# ATMega16U2-MU_1.net
KiCad netlist of a schematic drawn in Altium Designer
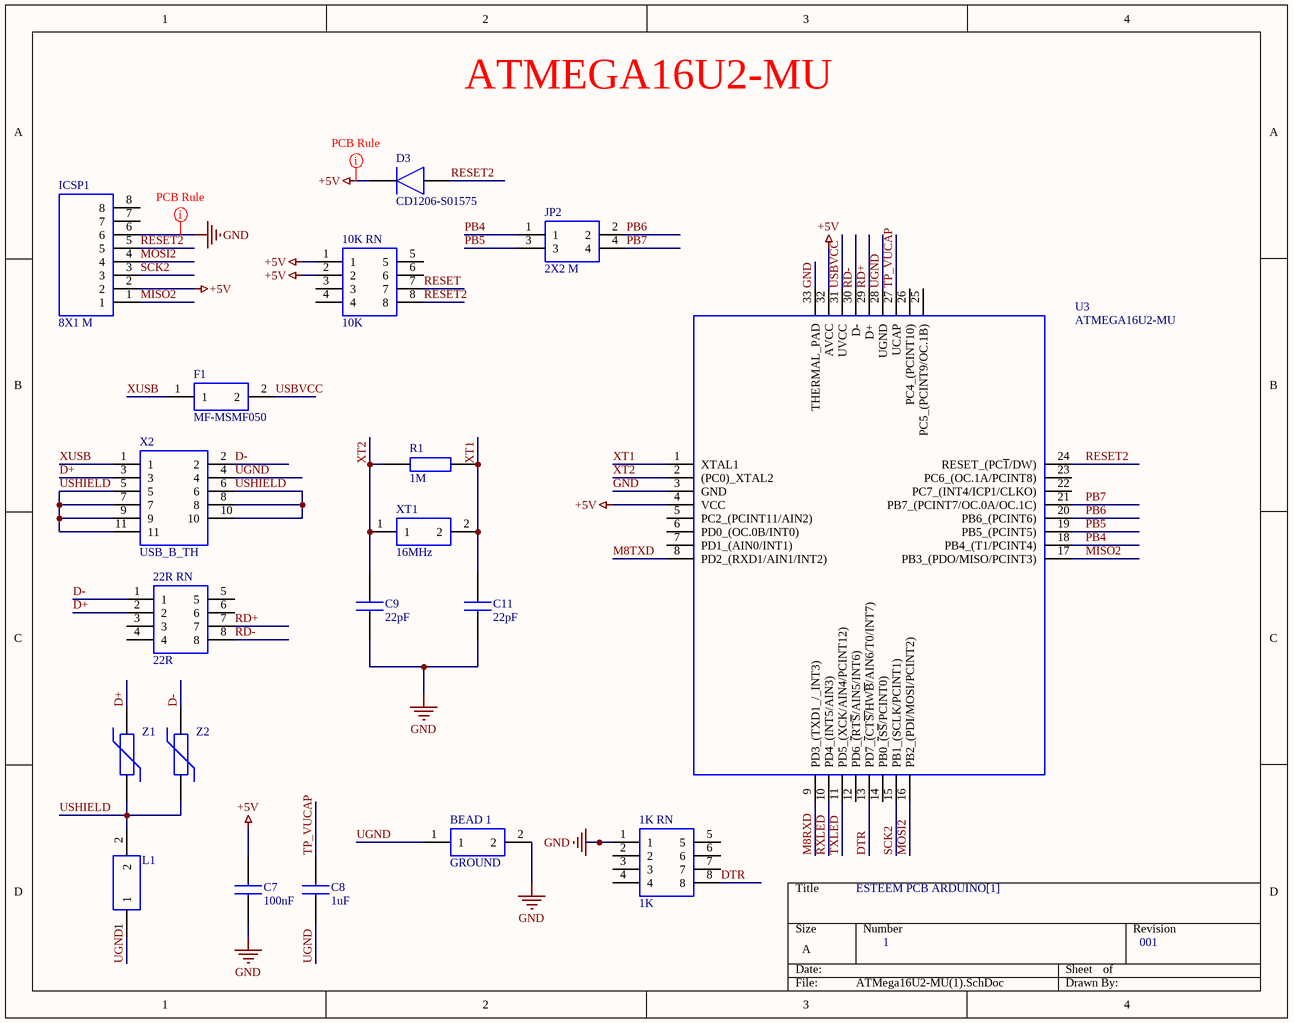
[diagram p0: ATMega16U2-MU(1).SchDoc]

(export (version "E")
  (design (tool "Eeschema 10.0.6"))
  (components
    (comp (ref "1K RN")
      (value "1K")
      (footprint "CAY10-XXXJ4")
      (fields
        (field (name "MANUFACTURER_PART_NUMBER") "CAY10-220J4LF")
        (field (name "RS PART NUMBER") "1674746")
        (field (name "MOUSER PART NUMBER") "652-CAY10-220J4LF")
      )
      (libsource (lib "10K RN1C") (part "CAY10-220J4LF"))
    )
    (comp (ref "10K RN")
      (value "10K")
      (footprint "CAY10-XXXJ4")
      (fields
        (field (name "MANUFACTURER_PART_NUMBER") "CAY10-220J4LF")
        (field (name "RS PART NUMBER") "1674746")
        (field (name "MOUSER PART NUMBER") "652-CAY10-220J4LF")
      )
      (libsource (lib "10K RN1C") (part "CAY10-220J4LF"))
    )
    (comp (ref "22R RN")
      (value "22R")
      (footprint "CAY10-XXXJ4")
      (fields
        (field (name "MANUFACTURER_PART_NUMBER") "CAY10-220J4LF")
        (field (name "RS PART NUMBER") "1674746")
        (field (name "MOUSER PART NUMBER") "652-CAY10-220J4LF")
      )
      (libsource (lib "22R RN3D") (part "CAY10-220J4LF"))
    )
    (comp (ref "BEAD 1")
      (value "GROUND")
      (footprint "BEADC2012X105N")
      (description "Chip Ferrite Bead 600R 0805 300mA 1LN")
      (fields
        (field (name "MANUFACTURER_PART_NUMBER") "BLM21BD601SH1D")
        (field (name "RS PART NUMBER") "1048541P")
      )
      (libsource (lib "Ferride Bead") (part "BLM21BD601SH1D"))
    )
    (comp (ref "C7")
      (value "100nF")
      (footprint "CAPC2012X130N")
      (fields
        (field (name "MANUFACTURER_PART_NUMBER") "0805Y0500104KXT")
        (field (name "RS PART NUMBER") "7738389P")
      )
      (libsource (lib "100nF") (part "0805Y0500104KXT"))
    )
    (comp (ref "C8")
      (value "1uF")
      (footprint "CAPC2012X145N")
      (description "Multilayer Ceramic Capacitors MLCC - SMD/SMT 0805 C0G 100volts 0.01uF 5% 1.25mm")
      (fields
        (field (name "MANUFACTURER_PART_NUMBER") "C2012C0G2A103J125AA")
        (field (name "MOUSER PART NUMBER") "810-C2012C0G2A103JAA")
      )
      (libsource (lib "1uF") (part "C2012C0G2A103J125AA"))
    )
    (comp (ref "C9")
      (value "22pF")
      (footprint "CAPC2012X70N")
      (description "MURATA - GRM2165C1H220JZ01D - CAP, MLCC, C0G/NP0, 22PF, 50V, 0805")
      (fields
        (field (name "MANUFACTURER_PART_NUMBER") "GRM2165C1H220JZ01D")
        (field (name "RS PART NUMBER") "7236243")
      )
      (libsource (lib "22pF") (part "GRM2165C1H220JZ01D"))
    )
    (comp (ref "C11")
      (value "22pF")
      (footprint "CAPC2012X70N")
      (description "MURATA - GRM2165C1H220JZ01D - CAP, MLCC, C0G/NP0, 22PF, 50V, 0805")
      (fields
        (field (name "MANUFACTURER_PART_NUMBER") "GRM2165C1H220JZ01D")
        (field (name "RS PART NUMBER") "7236243")
      )
      (libsource (lib "22pF") (part "GRM2165C1H220JZ01D"))
    )
    (comp (ref "D3")
      (value "CD1206-S01575")
      (footprint "DIOC3016X65N")
      (fields
        (field (name "RS PART NUMBER") "1775431")
        (field (name "MOUSER PART NUMBER") "652-CD1206-S01575")
      )
      (libsource (lib "CD1206-S01575") (part "CD1206-S01575"))
    )
    (comp (ref "F1")
      (value "MF-MSMF050")
      (footprint "FUSC4632X75N")
      (description "Littelfuse 0.5A Resettable Surface Mount Fuse, 30V dc")
      (fields
        (field (name "MANUFACTURER_PART_NUMBER") "1812L050/30PR")
        (field (name "RS PART NUMBER") "8951631P")
      )
      (libsource (lib "MF MSMF050-2 500mA") (part "1812L050_30PR"))
    )
    (comp (ref "ICSP1")
      (value "8X1 M")
      (footprint "HDRV8W90P0X254_1X8_2032X249X560P")
      (fields
        (field (name "MANUFACTURER_PART_NUMBER") "90120-0768")
        (field (name "RS PART NUMBER") "1671900")
        (field (name "MOUSER PART NUMBER") "538-90120-0768")
      )
      (libsource (lib "3x2 Male con") (part "90120-0768"))
    )
    (comp (ref "JP2")
      (value "2X2 M")
      (footprint "HDRV4W77P254_2X2_467X488X821P")
      (description "AMP - TE CONNECTIVITY - 5-146256-2 - CONNECTOR, HEADER, 4 POSITION, 2ROWS, 2.54MM")
      (fields
        (field (name "MANUFACTURER_PART_NUMBER") "5-146256-2")
        (field (name "RS PART NUMBER") "7972955")
      )
      (libsource (lib "2X2 Male") (part "5-146256-2"))
    )
    (comp (ref "L1")
      (value "BLM21BD601SH1D")
      (footprint "BEADC2012X105N")
      (description "Chip Ferrite Bead 600R 0805 300mA 1LN")
      (fields
        (field (name "RS PART NUMBER") "1048541P")
        (field (name "MOUSER PART NUMBER") "81-BLM21BD601SH1D")
      )
      (libsource (lib "BLM21") (part "BLM21BD601SH1D"))
    )
    (comp (ref "R1")
      (value "1M")
      (footprint "RESC1608X55N")
      (description "TE CONNECTIVITY - CPF0603B1M0E1 - RES, THIN FILM, 1M, 0.1%, 0.063W, 0603")
      (fields
        (field (name "MANUFACTURER_PART_NUMBER") "CPF0603B1M0E1")
        (field (name "MOUSER PART NUMBER") "279-CPF0603B1M0E1")
      )
      (libsource (lib "1MR") (part "CPF0603B1M0E1"))
    )
    (comp (ref "U3")
      (value "ATMEGA16U2-MU")
      (footprint "QFN50P500X500X100-33N-D")
      (description "8-bit Microcontrollers - MCU AVR USB 8K FLASH AVR USB 16K FLASH")
      (fields
        (field (name "RS PART NUMBER") "1717746")
        (field (name "MOUSER PART NUMBER") "556-ATMEGA16U2-MU")
      )
      (libsource (lib "ATMEGA16 U2-MU") (part "ATMEGA16U2-MU"))
    )
    (comp (ref "X2")
      (value "USB_B_TH")
      (footprint "17340351")
      (description "AMP - TE CONNECTIVITY - 1734035-1. - MINI USB, 2.0 TYPE B, RECEPTACLE, SMT")
      (fields
        (field (name "MANUFACTURER_PART_NUMBER") "1734035-1")
        (field (name "MOUSER PART NUMBER") "571-1734035-1")
      )
      (libsource (lib "USB type B TH") (part "1734035-1"))
    )
    (comp (ref "XT1")
      (value "16MHz")
      (footprint "MODEL-445")
      (description "Crystals 16MHz +/-30ppm 18pF -40C +85C")
      (fields
        (field (name "MANUFACTURER_PART_NUMBER") "445I35D16M00000")
        (field (name "MOUSER PART NUMBER") "774-445I35D16M00000")
      )
      (libsource (lib "16Mhz") (part "445I35D16M00000"))
    )
    (comp (ref "Z1")
      (value "CG0603MLC")
      (footprint "VARC1608X55N")
      (description "Varistor, ESD Protector, 5VDC,20V,0603 Bourns MLC Series Power Varistor 0.5pF 20V 0603 Case")
      (fields
        (field (name "MANUFACTURER_PART_NUMBER") "CG0603MLC-05E")
        (field (name "RS PART NUMBER") "8518256")
      )
      (libsource (lib "CG0603MLC-05E") (part "CG0603MLC-05E"))
    )
    (comp (ref "Z2")
      (value "CG0603MLC-05E")
      (footprint "VARC1608X55N")
      (description "Varistor, ESD Protector, 5VDC,20V,0603 Bourns MLC Series Power Varistor 0.5pF 20V 0603 Case")
      (fields
        (field (name "RS PART NUMBER") "8518256")
        (field (name "MOUSER PART NUMBER") "652-CG0603MLC-05E")
      )
      (libsource (lib "CG0603MLC-05E") (part "CG0603MLC-05E"))
    )
  )
  (nets
    (net (code "1") (name "+5V") (class "Default")
      (node (ref "10K RN") (pin "1") (pinfunction "1_1") (pintype "passive"))
      (node (ref "10K RN") (pin "2") (pinfunction "2_2") (pintype "passive"))
      (node (ref "C7") (pin "2") (pinfunction "2_2") (pintype "passive"))
      (node (ref "D3") (pin "1") (pinfunction "K_1") (pintype "passive"))
      (node (ref "ICSP1") (pin "2") (pinfunction "2_2") (pintype "passive"))
      (node (ref "U3") (pin "32") (pinfunction "AVCC_32") (pintype "passive"))
      (node (ref "U3") (pin "4") (pinfunction "VCC_4") (pintype "passive"))
    )
    (net (code "2") (name "/D+") (class "Default")
      (node (ref "22R RN") (pin "2") (pinfunction "2_2") (pintype "passive"))
      (node (ref "X2") (pin "3") (pinfunction "3_3") (pintype "passive"))
      (node (ref "Z1") (pin "2") (pinfunction "2_2") (pintype "passive"))
    )
    (net (code "3") (name "/D-") (class "Default")
      (node (ref "22R RN") (pin "1") (pinfunction "1_1") (pintype "passive"))
      (node (ref "X2") (pin "2") (pinfunction "2_2") (pintype "passive"))
      (node (ref "Z2") (pin "2") (pinfunction "2_2") (pintype "passive"))
    )
    (net (code "4") (name "/DTR") (class "Default")
      (node (ref "1K RN") (pin "8") (pinfunction "8_8") (pintype "passive"))
      (node (ref "U3") (pin "13") (pinfunction "PD7_~{(}CT~{S/}HW~{B}/AIN6/T0/INT7)_13") (pintype "passive"))
    )
    (net (code "5") (name "/M8RXD") (class "Default")
      (node (ref "U3") (pin "9") (pinfunction "PD3_(TXD1_/_INT3)_9") (pintype "passive"))
    )
    (net (code "6") (name "/M8TXD") (class "Default")
      (node (ref "U3") (pin "8") (pinfunction "PD2_(RXD1/AIN1/INT2)_8") (pintype "passive"))
    )
    (net (code "7") (name "/MISO2") (class "Default")
      (node (ref "ICSP1") (pin "1") (pinfunction "1_1") (pintype "passive"))
      (node (ref "U3") (pin "17") (pinfunction "PB3_(PDO/MISO/PCINT3)_17") (pintype "passive"))
    )
    (net (code "8") (name "/MOSI2") (class "Default")
      (node (ref "ICSP1") (pin "4") (pinfunction "4_4") (pintype "passive"))
      (node (ref "U3") (pin "16") (pinfunction "PB2_(PDI/MOSI/PCINT2)_16") (pintype "passive"))
    )
    (net (code "9") (name "/PB4") (class "Default")
      (node (ref "JP2") (pin "1") (pinfunction "1_1") (pintype "passive"))
      (node (ref "U3") (pin "18") (pinfunction "PB4_(T1/PCINT4)_18") (pintype "passive"))
    )
    (net (code "10") (name "/PB5") (class "Default")
      (node (ref "JP2") (pin "3") (pinfunction "3_3") (pintype "passive"))
      (node (ref "U3") (pin "19") (pinfunction "PB5_(PCINT5)_19") (pintype "passive"))
    )
    (net (code "11") (name "/PB6") (class "Default")
      (node (ref "JP2") (pin "2") (pinfunction "2_2") (pintype "passive"))
      (node (ref "U3") (pin "20") (pinfunction "PB6_(PCINT6)_20") (pintype "passive"))
    )
    (net (code "12") (name "/PB7") (class "Default")
      (node (ref "JP2") (pin "4") (pinfunction "4_4") (pintype "passive"))
      (node (ref "U3") (pin "21") (pinfunction "PB7_(PCINT7/OC.0A/OC.1C)_21") (pintype "passive"))
    )
    (net (code "13") (name "/RD+") (class "Default")
      (node (ref "22R RN") (pin "7") (pinfunction "7_7") (pintype "passive"))
      (node (ref "U3") (pin "29") (pinfunction "D+_29") (pintype "passive"))
    )
    (net (code "14") (name "/RD-") (class "Default")
      (node (ref "22R RN") (pin "8") (pinfunction "8_8") (pintype "passive"))
      (node (ref "U3") (pin "30") (pinfunction "D-_30") (pintype "passive"))
    )
    (net (code "15") (name "/RESET") (class "Default")
      (node (ref "10K RN") (pin "7") (pinfunction "7_7") (pintype "passive"))
    )
    (net (code "16") (name "/RESET2") (class "Default")
      (node (ref "10K RN") (pin "8") (pinfunction "8_8") (pintype "passive"))
      (node (ref "D3") (pin "2") (pinfunction "A_2") (pintype "passive"))
      (node (ref "ICSP1") (pin "5") (pinfunction "5_5") (pintype "passive"))
      (node (ref "U3") (pin "24") (pinfunction "RESET_(PC~{1}/DW)_24") (pintype "passive"))
    )
    (net (code "17") (name "/RXLED") (class "Default")
      (node (ref "U3") (pin "10") (pinfunction "PD4_(INT5/AIN3)_10") (pintype "passive"))
    )
    (net (code "18") (name "/SCK2") (class "Default")
      (node (ref "ICSP1") (pin "3") (pinfunction "3_3") (pintype "passive"))
      (node (ref "U3") (pin "15") (pinfunction "PB1_(SCLK/PCINT1)_15") (pintype "passive"))
    )
    (net (code "19") (name "/TP_VUCAP") (class "Default")
      (node (ref "C8") (pin "2") (pinfunction "2_2") (pintype "passive"))
      (node (ref "U3") (pin "27") (pinfunction "UCAP_27") (pintype "passive"))
    )
    (net (code "20") (name "/TXLED") (class "Default")
      (node (ref "U3") (pin "11") (pinfunction "PD5_(XCK/AIN4/PCINT12)_11") (pintype "passive"))
    )
    (net (code "21") (name "/UGND") (class "Default")
      (node (ref "BEAD 1") (pin "1") (pinfunction "1_1") (pintype "passive"))
      (node (ref "C8") (pin "1") (pinfunction "1_1") (pintype "passive"))
      (node (ref "L1") (pin "1") (pinfunction "1_1") (pintype "passive"))
      (node (ref "U3") (pin "28") (pinfunction "UGND_28") (pintype "passive"))
      (node (ref "X2") (pin "4") (pinfunction "4_4") (pintype "passive"))
    )
    (net (code "22") (name "/USBVCC") (class "Default")
      (node (ref "F1") (pin "2") (pinfunction "2_2") (pintype "passive"))
      (node (ref "U3") (pin "31") (pinfunction "UVCC_31") (pintype "passive"))
    )
    (net (code "23") (name "/USHIELD") (class "Default")
      (node (ref "L1") (pin "2") (pinfunction "2_2") (pintype "passive"))
      (node (ref "X2") (pin "10") (pinfunction "10_10") (pintype "passive"))
      (node (ref "X2") (pin "11") (pinfunction "11_11") (pintype "passive"))
      (node (ref "X2") (pin "5") (pinfunction "5_5") (pintype "passive"))
      (node (ref "X2") (pin "6") (pinfunction "6_6") (pintype "passive"))
      (node (ref "X2") (pin "7") (pinfunction "7_7") (pintype "passive"))
      (node (ref "X2") (pin "8") (pinfunction "8_8") (pintype "passive"))
      (node (ref "X2") (pin "9") (pinfunction "9_9") (pintype "passive"))
      (node (ref "Z1") (pin "1") (pinfunction "1_1") (pintype "passive"))
      (node (ref "Z2") (pin "1") (pinfunction "1_1") (pintype "passive"))
    )
    (net (code "24") (name "/XT1") (class "Default")
      (node (ref "C11") (pin "2") (pinfunction "2_2") (pintype "passive"))
      (node (ref "R1") (pin "2") (pinfunction "2_2") (pintype "passive"))
      (node (ref "U3") (pin "1") (pinfunction "XTAL1_1") (pintype "passive"))
      (node (ref "XT1") (pin "2") (pinfunction "2_2") (pintype "passive"))
    )
    (net (code "25") (name "/XT2") (class "Default")
      (node (ref "C9") (pin "2") (pinfunction "2_2") (pintype "passive"))
      (node (ref "R1") (pin "1") (pinfunction "1_1") (pintype "passive"))
      (node (ref "U3") (pin "2") (pinfunction "(PC0)_XTAL2_2") (pintype "passive"))
      (node (ref "XT1") (pin "1") (pinfunction "1_1") (pintype "passive"))
    )
    (net (code "26") (name "/XUSB") (class "Default")
      (node (ref "F1") (pin "1") (pinfunction "1_1") (pintype "passive"))
      (node (ref "X2") (pin "1") (pinfunction "1_1") (pintype "passive"))
    )
    (net (code "27") (name "GND") (class "Default")
      (node (ref "1K RN") (pin "1") (pinfunction "1_1") (pintype "passive"))
      (node (ref "BEAD 1") (pin "2") (pinfunction "2_2") (pintype "passive"))
      (node (ref "C11") (pin "1") (pinfunction "1_1") (pintype "passive"))
      (node (ref "C7") (pin "1") (pinfunction "1_1") (pintype "passive"))
      (node (ref "C9") (pin "1") (pinfunction "1_1") (pintype "passive"))
      (node (ref "ICSP1") (pin "6") (pinfunction "6_6") (pintype "passive"))
      (node (ref "U3") (pin "3") (pinfunction "GND_3") (pintype "passive"))
      (node (ref "U3") (pin "33") (pinfunction "THERMAL_PAD_33") (pintype "passive"))
    )
    (net (code "28") (name "unconnected-(1K RN-Pad2)") (class "Default")
      (node (ref "1K RN") (pin "2") (pinfunction "2_2") (pintype "passive"))
    )
    (net (code "29") (name "unconnected-(1K RN-Pad3)") (class "Default")
      (node (ref "1K RN") (pin "3") (pinfunction "3_3") (pintype "passive"))
    )
    (net (code "30") (name "unconnected-(1K RN-Pad4)") (class "Default")
      (node (ref "1K RN") (pin "4") (pinfunction "4_4") (pintype "passive"))
    )
    (net (code "31") (name "unconnected-(1K RN-Pad5)") (class "Default")
      (node (ref "1K RN") (pin "5") (pinfunction "5_5") (pintype "passive"))
    )
    (net (code "32") (name "unconnected-(1K RN-Pad6)") (class "Default")
      (node (ref "1K RN") (pin "6") (pinfunction "6_6") (pintype "passive"))
    )
    (net (code "33") (name "unconnected-(1K RN-Pad7)") (class "Default")
      (node (ref "1K RN") (pin "7") (pinfunction "7_7") (pintype "passive"))
    )
    (net (code "34") (name "unconnected-(10K RN-Pad3)") (class "Default")
      (node (ref "10K RN") (pin "3") (pinfunction "3_3") (pintype "passive"))
    )
    (net (code "35") (name "unconnected-(10K RN-Pad4)") (class "Default")
      (node (ref "10K RN") (pin "4") (pinfunction "4_4") (pintype "passive"))
    )
    (net (code "36") (name "unconnected-(10K RN-Pad5)") (class "Default")
      (node (ref "10K RN") (pin "5") (pinfunction "5_5") (pintype "passive"))
    )
    (net (code "37") (name "unconnected-(10K RN-Pad6)") (class "Default")
      (node (ref "10K RN") (pin "6") (pinfunction "6_6") (pintype "passive"))
    )
    (net (code "38") (name "unconnected-(22R RN-Pad3)") (class "Default")
      (node (ref "22R RN") (pin "3") (pinfunction "3_3") (pintype "passive"))
    )
    (net (code "39") (name "unconnected-(22R RN-Pad4)") (class "Default")
      (node (ref "22R RN") (pin "4") (pinfunction "4_4") (pintype "passive"))
    )
    (net (code "40") (name "unconnected-(22R RN-Pad5)") (class "Default")
      (node (ref "22R RN") (pin "5") (pinfunction "5_5") (pintype "passive"))
    )
    (net (code "41") (name "unconnected-(22R RN-Pad6)") (class "Default")
      (node (ref "22R RN") (pin "6") (pinfunction "6_6") (pintype "passive"))
    )
    (net (code "42") (name "unconnected-(ICSP1-Pad7)") (class "Default")
      (node (ref "ICSP1") (pin "7") (pinfunction "7_7") (pintype "passive"))
    )
    (net (code "43") (name "unconnected-(ICSP1-Pad8)") (class "Default")
      (node (ref "ICSP1") (pin "8") (pinfunction "8_8") (pintype "passive"))
    )
    (net (code "44") (name "unconnected-(U3-PB0_~{(}S~{S}{slash}PCINT0)-Pad14)") (class "Default")
      (node (ref "U3") (pin "14") (pinfunction "PB0_~{(}S~{S}/PCINT0)_14") (pintype "passive"))
    )
    (net (code "45") (name "unconnected-(U3-PC2_(PCINT11{slash}AIN2)-Pad5)") (class "Default")
      (node (ref "U3") (pin "5") (pinfunction "PC2_(PCINT11/AIN2)_5") (pintype "passive"))
    )
    (net (code "46") (name "unconnected-(U3-PC4_(PCINT10)-Pad26)") (class "Default")
      (node (ref "U3") (pin "26") (pinfunction "PC4_(PCINT10)_26") (pintype "passive"))
    )
    (net (code "47") (name "unconnected-(U3-PC5_(PCINT9{slash}OC.1B)-Pad25)") (class "Default")
      (node (ref "U3") (pin "25") (pinfunction "PC5_(PCINT9/OC.1B)_25") (pintype "passive"))
    )
    (net (code "48") (name "unconnected-(U3-PC6_(OC.1A{slash}PCINT8)-Pad23)") (class "Default")
      (node (ref "U3") (pin "23") (pinfunction "PC6_(OC.1A/PCINT8)_23") (pintype "passive"))
    )
    (net (code "49") (name "unconnected-(U3-PC7_(INT4{slash}ICP1{slash}CLKO)-Pad22)") (class "Default")
      (node (ref "U3") (pin "22") (pinfunction "PC7_(INT4/ICP1/CLKO)_22") (pintype "passive"))
    )
    (net (code "50") (name "unconnected-(U3-PD0_(OC.0B{slash}INT0)-Pad6)") (class "Default")
      (node (ref "U3") (pin "6") (pinfunction "PD0_(OC.0B/INT0)_6") (pintype "passive"))
    )
    (net (code "51") (name "unconnected-(U3-PD1_(AIN0{slash}INT1)-Pad7)") (class "Default")
      (node (ref "U3") (pin "7") (pinfunction "PD1_(AIN0/INT1)_7") (pintype "passive"))
    )
    (net (code "52") (name "unconnected-(U3-PD6_~{(}RT~{S}{slash}AIN5{slash}INT6)-Pad12)") (class "Default")
      (node (ref "U3") (pin "12") (pinfunction "PD6_~{(}RT~{S}/AIN5/INT6)_12") (pintype "passive"))
    )
  )
)
